# ibmpc.net
KiCad netlist of a schematic drawn in EAGLE
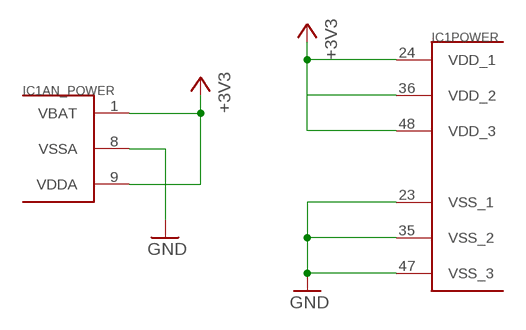
[diagram p0: schematic, sheet 1, part 1 of 2]
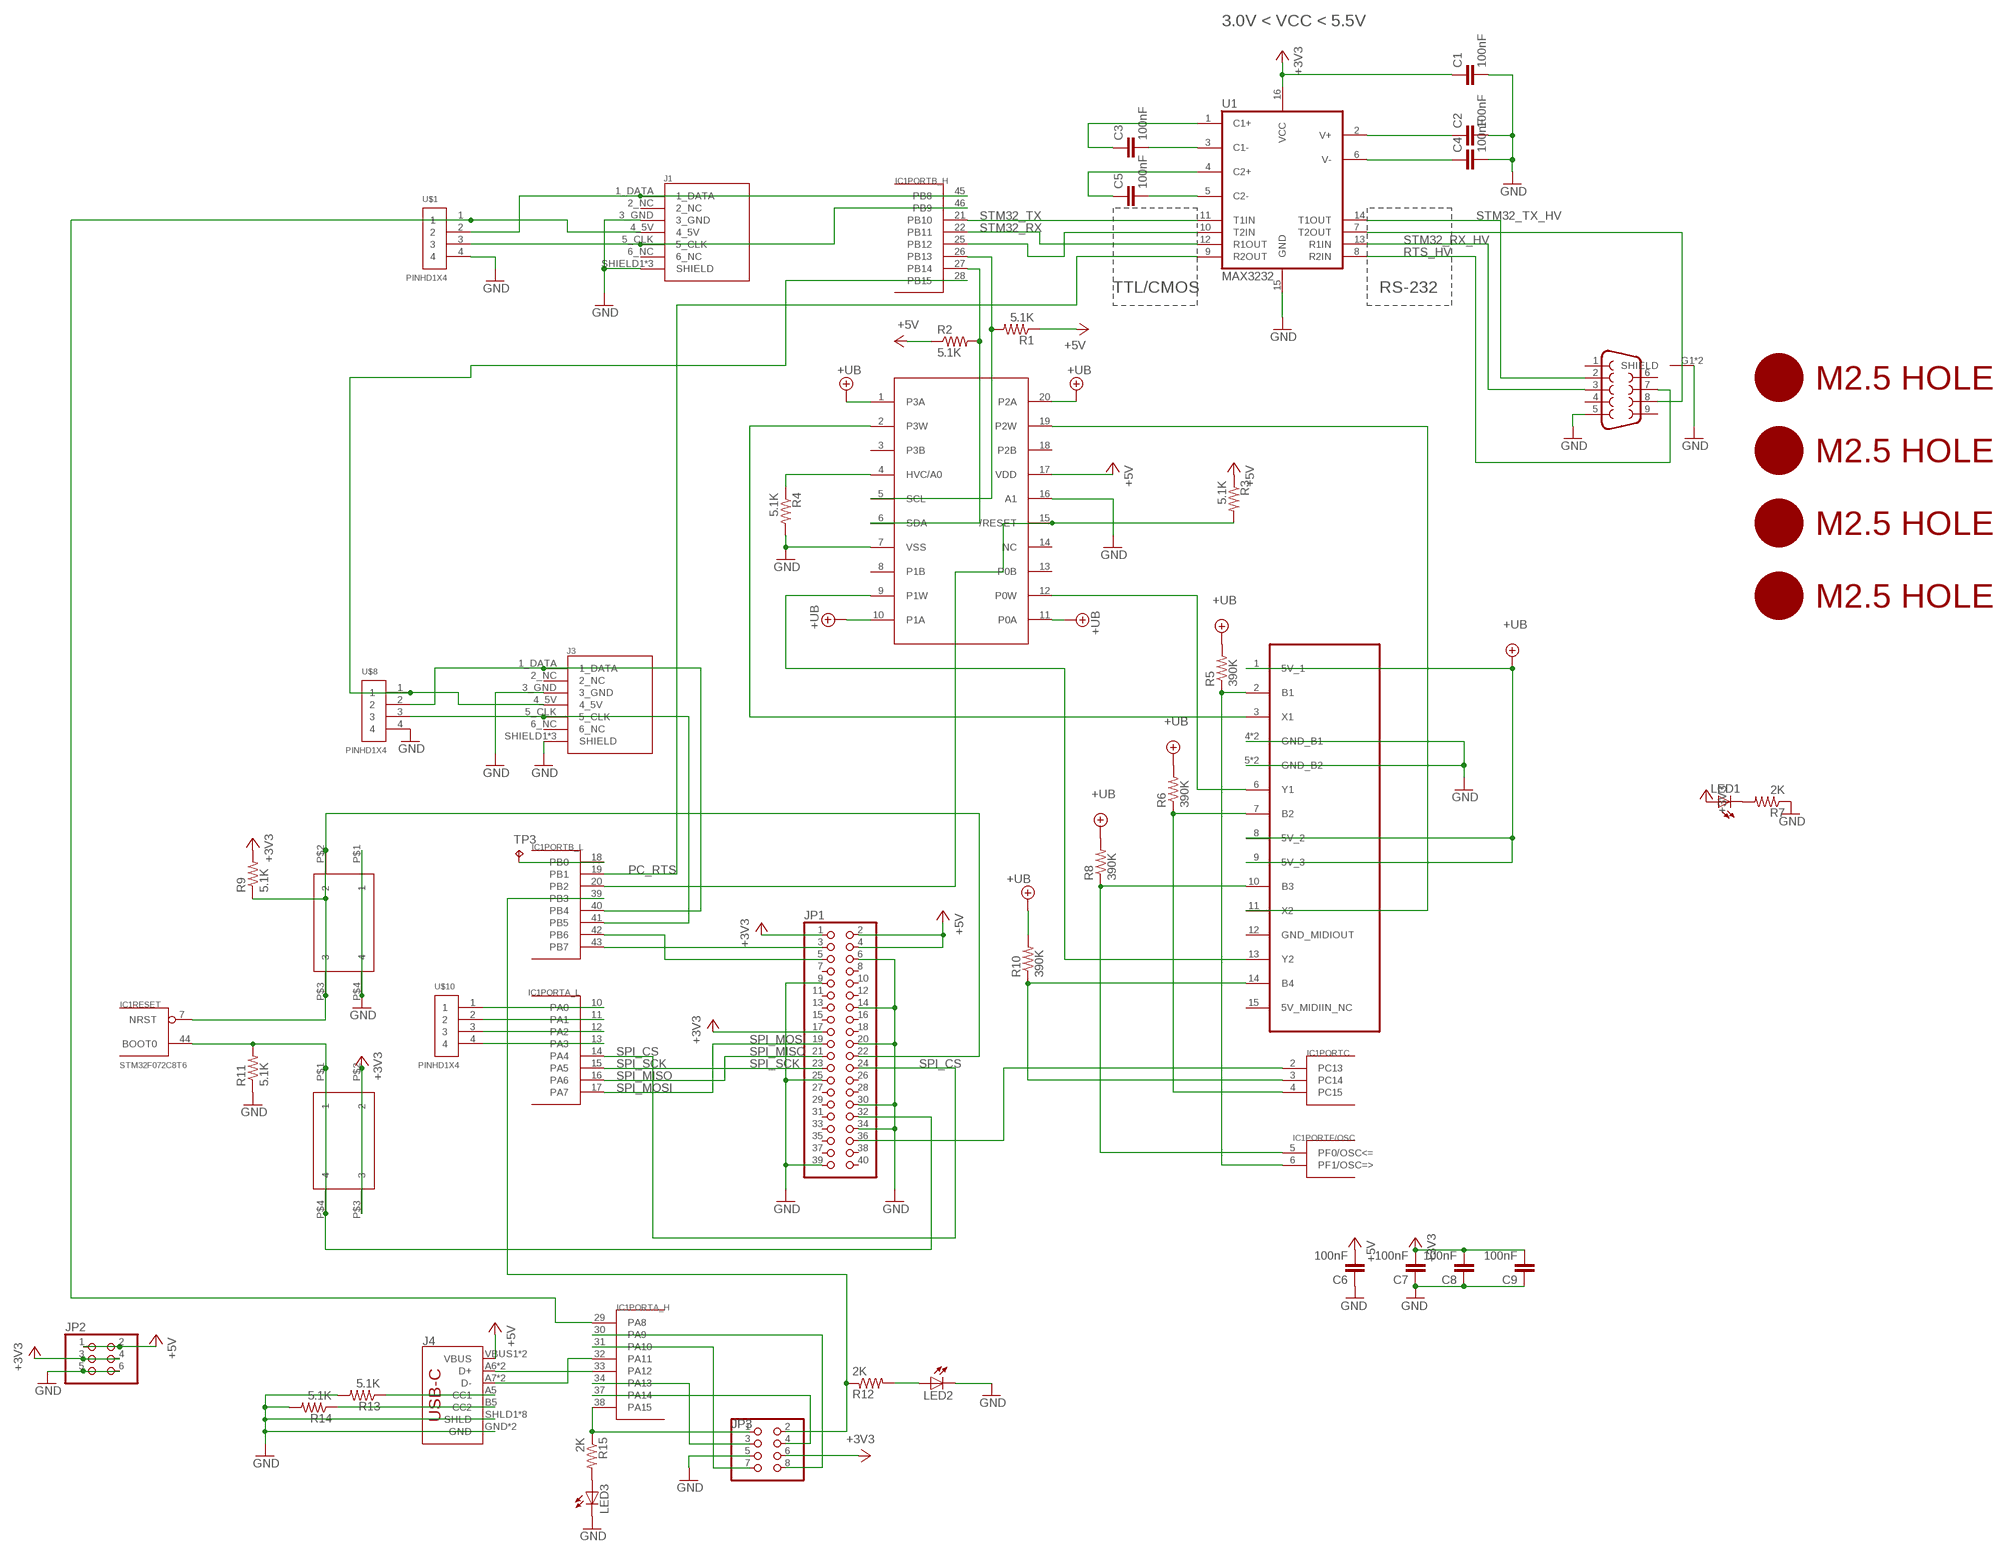
[diagram p1: schematic, sheet 1, part 2 of 2]

(export (version "E")
  (design (tool "Eeschema 10.0.6"))
  (components
    (comp (ref "C1")
      (value "100nF")
      (footprint "eagle-import:0805@1")
      (libsource (lib "eagle-import") (part "CAP0805"))
    )
    (comp (ref "C2")
      (value "100nF")
      (footprint "eagle-import:0805@1")
      (libsource (lib "eagle-import") (part "CAP0805"))
    )
    (comp (ref "C3")
      (value "100nF")
      (footprint "eagle-import:0805@1")
      (libsource (lib "eagle-import") (part "CAP0805"))
    )
    (comp (ref "C4")
      (value "100nF")
      (footprint "eagle-import:0805@1")
      (libsource (lib "eagle-import") (part "CAP0805"))
    )
    (comp (ref "C5")
      (value "100nF")
      (footprint "eagle-import:0805@1")
      (libsource (lib "eagle-import") (part "CAP0805"))
    )
    (comp (ref "C6")
      (value "100nF")
      (footprint "eagle-import:0805@1")
      (libsource (lib "eagle-import") (part "CAP0805"))
    )
    (comp (ref "C7")
      (value "100nF")
      (footprint "eagle-import:0805@1")
      (libsource (lib "eagle-import") (part "CAP0805"))
    )
    (comp (ref "C8")
      (value "100nF")
      (footprint "eagle-import:0805@1")
      (libsource (lib "eagle-import") (part "CAP0805"))
    )
    (comp (ref "C9")
      (value "100nF")
      (footprint "eagle-import:0805@1")
      (libsource (lib "eagle-import") (part "CAP0805"))
    )
    (comp (ref "IC1")
      (value "STM32F072C8T6")
      (footprint "eagle-import:TQFP48")
      (libsource (lib "eagle-import") (part "STM32F072C8T6"))
    )
    (comp (ref "J1")
      (value "DIN7")
      (footprint "eagle-import:DIN7")
      (libsource (lib "eagle-import") (part "DIN7"))
    )
    (comp (ref "J2")
      (value "DB9MALE")
      (footprint "eagle-import:DB9_MALE")
      (libsource (lib "eagle-import") (part "DB9MALE"))
    )
    (comp (ref "J3")
      (value "DIN7")
      (footprint "eagle-import:DIN7")
      (libsource (lib "eagle-import") (part "DIN7"))
    )
    (comp (ref "J4")
      (value "USB_C16PIN")
      (footprint "eagle-import:USB-C-16P")
      (libsource (lib "eagle-import") (part "USB_C16PIN"))
    )
    (comp (ref "JP1")
      (value "PINHD-2X20-BIG")
      (footprint "eagle-import:2X20-BIG")
      (libsource (lib "eagle-import") (part "PINHD-2X20-BIG"))
    )
    (comp (ref "JP2")
      (value "PINHD-2X3")
      (footprint "eagle-import:2X03")
      (libsource (lib "eagle-import") (part "PINHD-2X3"))
    )
    (comp (ref "JP3")
      (value "PINHD-2X4")
      (footprint "eagle-import:2X04")
      (libsource (lib "eagle-import") (part "PINHD-2X4"))
    )
    (comp (ref "LED1")
      (value "LEDCHIP-LED0805")
      (footprint "eagle-import:CHIP-LED0805")
      (libsource (lib "eagle-import") (part "LEDCHIP-LED0805"))
    )
    (comp (ref "LED2")
      (value "LEDCHIP-LED0805")
      (footprint "eagle-import:CHIP-LED0805")
      (libsource (lib "eagle-import") (part "LEDCHIP-LED0805"))
    )
    (comp (ref "LED3")
      (value "LEDCHIP-LED0805")
      (footprint "eagle-import:CHIP-LED0805")
      (libsource (lib "eagle-import") (part "LEDCHIP-LED0805"))
    )
    (comp (ref "R1")
      (value "5.1K")
      (footprint "eagle-import:0805")
      (libsource (lib "eagle-import") (part "RESISTOR0805-RES"))
    )
    (comp (ref "R2")
      (value "5.1K")
      (footprint "eagle-import:0805")
      (libsource (lib "eagle-import") (part "RESISTOR0805-RES"))
    )
    (comp (ref "R3")
      (value "5.1K")
      (footprint "eagle-import:0805")
      (libsource (lib "eagle-import") (part "RESISTOR0805-RES"))
    )
    (comp (ref "R4")
      (value "5.1K")
      (footprint "eagle-import:0805")
      (libsource (lib "eagle-import") (part "RESISTOR0805-RES"))
    )
    (comp (ref "R5")
      (value "390K")
      (footprint "eagle-import:0805")
      (libsource (lib "eagle-import") (part "RESISTOR0805-RES"))
    )
    (comp (ref "R6")
      (value "390K")
      (footprint "eagle-import:0805")
      (libsource (lib "eagle-import") (part "RESISTOR0805-RES"))
    )
    (comp (ref "R7")
      (value "2K")
      (footprint "eagle-import:0805")
      (libsource (lib "eagle-import") (part "RESISTOR0805-RES"))
    )
    (comp (ref "R8")
      (value "390K")
      (footprint "eagle-import:0805")
      (libsource (lib "eagle-import") (part "RESISTOR0805-RES"))
    )
    (comp (ref "R9")
      (value "5.1K")
      (footprint "eagle-import:0805")
      (libsource (lib "eagle-import") (part "RESISTOR0805-RES"))
    )
    (comp (ref "R10")
      (value "390K")
      (footprint "eagle-import:0805")
      (libsource (lib "eagle-import") (part "RESISTOR0805-RES"))
    )
    (comp (ref "R11")
      (value "5.1K")
      (footprint "eagle-import:0805")
      (libsource (lib "eagle-import") (part "RESISTOR0805-RES"))
    )
    (comp (ref "R12")
      (value "2K")
      (footprint "eagle-import:0805")
      (libsource (lib "eagle-import") (part "RESISTOR0805-RES"))
    )
    (comp (ref "R13")
      (value "5.1K")
      (footprint "eagle-import:0805")
      (libsource (lib "eagle-import") (part "RESISTOR0805-RES"))
    )
    (comp (ref "R14")
      (value "5.1K")
      (footprint "eagle-import:0805")
      (libsource (lib "eagle-import") (part "RESISTOR0805-RES"))
    )
    (comp (ref "R15")
      (value "2K")
      (footprint "eagle-import:0805")
      (libsource (lib "eagle-import") (part "RESISTOR0805-RES"))
    )
    (comp (ref "SW1")
      (value "324_SW")
      (footprint "eagle-import:342_SWICH_FOOT")
      (libsource (lib "eagle-import") (part "324_SW"))
    )
    (comp (ref "SW2")
      (value "324_SW")
      (footprint "eagle-import:342_SWICH_FOOT")
      (libsource (lib "eagle-import") (part "324_SW"))
    )
    (comp (ref "TP3")
      (value "TPTP12R")
      (footprint "eagle-import:TP12R")
      (libsource (lib "eagle-import") (part "TPTP12R"))
    )
    (comp (ref "U$1")
      (value "PINHD1X4")
      (footprint "eagle-import:1X04-CLEANBIG")
      (libsource (lib "eagle-import") (part "PINHD1X4"))
    )
    (comp (ref "U$2")
      (value "M2.5HOLE")
      (footprint "eagle-import:M2.5HOLE")
      (libsource (lib "eagle-import") (part "M2.5HOLE"))
    )
    (comp (ref "U$3")
      (value "M2.5HOLE")
      (footprint "eagle-import:M2.5HOLE")
      (libsource (lib "eagle-import") (part "M2.5HOLE"))
    )
    (comp (ref "U$5")
      (value "MCP4451")
      (footprint "eagle-import:TSSOP20")
      (libsource (lib "eagle-import") (part "MCP4451"))
    )
    (comp (ref "U$6")
      (value "M2.5HOLE")
      (footprint "eagle-import:M2.5HOLE")
      (libsource (lib "eagle-import") (part "M2.5HOLE"))
    )
    (comp (ref "U$7")
      (value "M2.5HOLE")
      (footprint "eagle-import:M2.5HOLE")
      (libsource (lib "eagle-import") (part "M2.5HOLE"))
    )
    (comp (ref "U$8")
      (value "PINHD1X4")
      (footprint "eagle-import:1X04-CLEANBIG")
      (libsource (lib "eagle-import") (part "PINHD1X4"))
    )
    (comp (ref "U$9")
      (value "GAMEPORT_15P")
      (footprint "eagle-import:DA15")
      (libsource (lib "eagle-import") (part "GAMEPORT_15P"))
    )
    (comp (ref "U$10")
      (value "PINHD1X4")
      (footprint "eagle-import:1X04-CLEANBIG")
      (libsource (lib "eagle-import") (part "PINHD1X4"))
    )
    (comp (ref "U1")
      (value "MAX3232")
      (footprint "eagle-import:SO016")
      (libsource (lib "eagle-import") (part "MAX232SOIC16"))
    )
  )
  (nets
    (net (code "1") (name "+3V3") (class "Default")
      (node (ref "C1") (pin "1") (pinfunction "1_1") (pintype "passive"))
      (node (ref "C7") (pin "2") (pinfunction "2_2") (pintype "passive"))
      (node (ref "C8") (pin "2") (pinfunction "2_2") (pintype "passive"))
      (node (ref "C9") (pin "2") (pinfunction "2_2") (pintype "passive"))
      (node (ref "IC1") (pin "1") (pinfunction "VBAT_1") (pintype "power_in"))
      (node (ref "IC1") (pin "24") (pinfunction "VDD_1_24") (pintype "power_in"))
      (node (ref "IC1") (pin "36") (pinfunction "VDD_2_36") (pintype "power_in"))
      (node (ref "IC1") (pin "48") (pinfunction "VDD_3_48") (pintype "power_in"))
      (node (ref "IC1") (pin "9") (pinfunction "VDDA_9") (pintype "power_in"))
      (node (ref "JP1") (pin "1") (pinfunction "1_1") (pintype "passive"))
      (node (ref "JP1") (pin "17") (pinfunction "17_17") (pintype "passive"))
      (node (ref "JP2") (pin "3") (pinfunction "3_3") (pintype "passive"))
      (node (ref "JP2") (pin "4") (pinfunction "4_4") (pintype "passive"))
      (node (ref "JP3") (pin "6") (pinfunction "6_6") (pintype "passive"))
      (node (ref "LED1") (pin "A") (pinfunction "A_A") (pintype "passive"))
      (node (ref "R9") (pin "2") (pinfunction "2_2") (pintype "passive"))
      (node (ref "SW2") (pin "P$2") (pinfunction "2_P$2") (pintype "bidirectional"))
      (node (ref "SW2") (pin "P$3") (pinfunction "3_P$3") (pintype "bidirectional"))
      (node (ref "U1") (pin "16") (pinfunction "VCC_16") (pintype "bidirectional"))
    )
    (net (code "2") (name "+5V") (class "Default")
      (node (ref "C6") (pin "2") (pinfunction "2_2") (pintype "passive"))
      (node (ref "J4") (pin "VBUS1") (pinfunction "VBUS_VBUS1") (pintype "bidirectional"))
      (node (ref "J4") (pin "VBUS2") (pinfunction "VBUS_VBUS2") (pintype "bidirectional"))
      (node (ref "JP1") (pin "2") (pinfunction "2_2") (pintype "passive"))
      (node (ref "JP1") (pin "4") (pinfunction "4_4") (pintype "passive"))
      (node (ref "JP2") (pin "1") (pinfunction "1_1") (pintype "passive"))
      (node (ref "JP2") (pin "2") (pinfunction "2_2") (pintype "passive"))
      (node (ref "R1") (pin "1") (pinfunction "1_1") (pintype "passive"))
      (node (ref "R2") (pin "1") (pinfunction "1_1") (pintype "passive"))
      (node (ref "R3") (pin "1") (pinfunction "1_1") (pintype "passive"))
      (node (ref "U$5") (pin "17") (pinfunction "VDD_17") (pintype "bidirectional"))
    )
    (net (code "3") (name "+UB") (class "Default")
      (node (ref "R10") (pin "2") (pinfunction "2_2") (pintype "passive"))
      (node (ref "R5") (pin "2") (pinfunction "2_2") (pintype "passive"))
      (node (ref "R6") (pin "2") (pinfunction "2_2") (pintype "passive"))
      (node (ref "R8") (pin "2") (pinfunction "2_2") (pintype "passive"))
      (node (ref "U$5") (pin "1") (pinfunction "P3A_1") (pintype "bidirectional"))
      (node (ref "U$5") (pin "10") (pinfunction "P1A_10") (pintype "bidirectional"))
      (node (ref "U$5") (pin "11") (pinfunction "P0A_11") (pintype "bidirectional"))
      (node (ref "U$5") (pin "20") (pinfunction "P2A_20") (pintype "bidirectional"))
      (node (ref "U$9") (pin "1") (pinfunction "5V_1_1") (pintype "bidirectional"))
      (node (ref "U$9") (pin "8") (pinfunction "5V_2_8") (pintype "bidirectional"))
      (node (ref "U$9") (pin "9") (pinfunction "5V_3_9") (pintype "bidirectional"))
    )
    (net (code "4") (name "/PC_RTS") (class "Default")
      (node (ref "IC1") (pin "19") (pinfunction "PB1_19") (pintype "bidirectional"))
      (node (ref "U1") (pin "9") (pinfunction "R2OUT_9") (pintype "output"))
    )
    (net (code "5") (name "/RTS_HV") (class "Default")
      (node (ref "J2") (pin "7") (pinfunction "7_7") (pintype "passive"))
      (node (ref "U1") (pin "8") (pinfunction "R2IN_8") (pintype "input"))
    )
    (net (code "6") (name "/SPI_CS") (class "Default")
      (node (ref "IC1") (pin "14") (pinfunction "PA4_14") (pintype "bidirectional"))
      (node (ref "JP1") (pin "24") (pinfunction "24_24") (pintype "passive"))
    )
    (net (code "7") (name "/SPI_MISO") (class "Default")
      (node (ref "IC1") (pin "16") (pinfunction "PA6_16") (pintype "bidirectional"))
      (node (ref "JP1") (pin "21") (pinfunction "21_21") (pintype "passive"))
    )
    (net (code "8") (name "/SPI_MOSI") (class "Default")
      (node (ref "IC1") (pin "17") (pinfunction "PA7_17") (pintype "bidirectional"))
      (node (ref "JP1") (pin "19") (pinfunction "19_19") (pintype "passive"))
    )
    (net (code "9") (name "/SPI_SCK") (class "Default")
      (node (ref "IC1") (pin "15") (pinfunction "PA5_15") (pintype "bidirectional"))
      (node (ref "JP1") (pin "23") (pinfunction "23_23") (pintype "passive"))
    )
    (net (code "10") (name "/STM32_RX") (class "Default")
      (node (ref "IC1") (pin "22") (pinfunction "PB11_22") (pintype "bidirectional"))
      (node (ref "U1") (pin "12") (pinfunction "R1OUT_12") (pintype "output"))
    )
    (net (code "11") (name "/STM32_RX_HV") (class "Default")
      (node (ref "J2") (pin "3") (pinfunction "3_3") (pintype "passive"))
      (node (ref "U1") (pin "13") (pinfunction "R1IN_13") (pintype "input"))
    )
    (net (code "12") (name "/STM32_TX") (class "Default")
      (node (ref "IC1") (pin "21") (pinfunction "PB10_21") (pintype "bidirectional"))
      (node (ref "U1") (pin "11") (pinfunction "T1IN_11") (pintype "input"))
    )
    (net (code "13") (name "/STM32_TX_HV") (class "Default")
      (node (ref "J2") (pin "2") (pinfunction "2_2") (pintype "passive"))
      (node (ref "U1") (pin "14") (pinfunction "T1OUT_14") (pintype "output"))
    )
    (net (code "14") (name "GND") (class "Default")
      (node (ref "C1") (pin "2") (pinfunction "2_2") (pintype "passive"))
      (node (ref "C2") (pin "2") (pinfunction "2_2") (pintype "passive"))
      (node (ref "C4") (pin "2") (pinfunction "2_2") (pintype "passive"))
      (node (ref "C6") (pin "1") (pinfunction "1_1") (pintype "passive"))
      (node (ref "C7") (pin "1") (pinfunction "1_1") (pintype "passive"))
      (node (ref "C8") (pin "1") (pinfunction "1_1") (pintype "passive"))
      (node (ref "C9") (pin "1") (pinfunction "1_1") (pintype "passive"))
      (node (ref "IC1") (pin "23") (pinfunction "VSS_1_23") (pintype "power_in"))
      (node (ref "IC1") (pin "35") (pinfunction "VSS_2_35") (pintype "power_in"))
      (node (ref "IC1") (pin "47") (pinfunction "VSS_3_47") (pintype "power_in"))
      (node (ref "IC1") (pin "8") (pinfunction "VSSA_8") (pintype "power_in"))
      (node (ref "J1") (pin "3_GND") (pinfunction "3_GND_3_GND") (pintype "bidirectional"))
      (node (ref "J1") (pin "SHIELD1") (pinfunction "SHIELD_SHIELD1") (pintype "bidirectional"))
      (node (ref "J1") (pin "SHIELD2") (pinfunction "SHIELD_SHIELD2") (pintype "bidirectional"))
      (node (ref "J1") (pin "SHIELD3") (pinfunction "SHIELD_SHIELD3") (pintype "bidirectional"))
      (node (ref "J2") (pin "5") (pinfunction "5_5") (pintype "passive"))
      (node (ref "J2") (pin "G1") (pinfunction "SHIELD_G1") (pintype "bidirectional"))
      (node (ref "J2") (pin "G2") (pinfunction "SHIELD_G2") (pintype "bidirectional"))
      (node (ref "J3") (pin "3_GND") (pinfunction "3_GND_3_GND") (pintype "bidirectional"))
      (node (ref "J3") (pin "SHIELD1") (pinfunction "SHIELD_SHIELD1") (pintype "bidirectional"))
      (node (ref "J3") (pin "SHIELD2") (pinfunction "SHIELD_SHIELD2") (pintype "bidirectional"))
      (node (ref "J3") (pin "SHIELD3") (pinfunction "SHIELD_SHIELD3") (pintype "bidirectional"))
      (node (ref "J4") (pin "GND") (pinfunction "GND_GND") (pintype "bidirectional"))
      (node (ref "J4") (pin "GND2") (pinfunction "GND_GND2") (pintype "bidirectional"))
      (node (ref "J4") (pin "SHLD1") (pinfunction "SHLD_SHLD1") (pintype "bidirectional"))
      (node (ref "J4") (pin "SHLD2") (pinfunction "SHLD_SHLD2") (pintype "bidirectional"))
      (node (ref "J4") (pin "SHLD3") (pinfunction "SHLD_SHLD3") (pintype "bidirectional"))
      (node (ref "J4") (pin "SHLD4") (pinfunction "SHLD_SHLD4") (pintype "bidirectional"))
      (node (ref "J4") (pin "SHLD5") (pinfunction "SHLD_SHLD5") (pintype "bidirectional"))
      (node (ref "J4") (pin "SHLD6") (pinfunction "SHLD_SHLD6") (pintype "bidirectional"))
      (node (ref "J4") (pin "SHLD7") (pinfunction "SHLD_SHLD7") (pintype "bidirectional"))
      (node (ref "J4") (pin "SHLD8") (pinfunction "SHLD_SHLD8") (pintype "bidirectional"))
      (node (ref "JP1") (pin "14") (pinfunction "14_14") (pintype "passive"))
      (node (ref "JP1") (pin "20") (pinfunction "20_20") (pintype "passive"))
      (node (ref "JP1") (pin "25") (pinfunction "25_25") (pintype "passive"))
      (node (ref "JP1") (pin "30") (pinfunction "30_30") (pintype "passive"))
      (node (ref "JP1") (pin "34") (pinfunction "34_34") (pintype "passive"))
      (node (ref "JP1") (pin "39") (pinfunction "39_39") (pintype "passive"))
      (node (ref "JP1") (pin "6") (pinfunction "6_6") (pintype "passive"))
      (node (ref "JP1") (pin "9") (pinfunction "9_9") (pintype "passive"))
      (node (ref "JP2") (pin "5") (pinfunction "5_5") (pintype "passive"))
      (node (ref "JP2") (pin "6") (pinfunction "6_6") (pintype "passive"))
      (node (ref "JP3") (pin "5") (pinfunction "5_5") (pintype "passive"))
      (node (ref "LED2") (pin "C") (pinfunction "C_C") (pintype "passive"))
      (node (ref "LED3") (pin "C") (pinfunction "C_C") (pintype "passive"))
      (node (ref "R11") (pin "1") (pinfunction "1_1") (pintype "passive"))
      (node (ref "R13") (pin "2") (pinfunction "2_2") (pintype "passive"))
      (node (ref "R14") (pin "2") (pinfunction "2_2") (pintype "passive"))
      (node (ref "R4") (pin "2") (pinfunction "2_2") (pintype "passive"))
      (node (ref "R7") (pin "1") (pinfunction "1_1") (pintype "passive"))
      (node (ref "SW1") (pin "P$1") (pinfunction "1_P$1") (pintype "bidirectional"))
      (node (ref "SW1") (pin "P$4") (pinfunction "4_P$4") (pintype "bidirectional"))
      (node (ref "U$1") (pin "4") (pinfunction "4_4") (pintype "bidirectional"))
      (node (ref "U$5") (pin "16") (pinfunction "A1_16") (pintype "bidirectional"))
      (node (ref "U$5") (pin "7") (pinfunction "VSS_7") (pintype "bidirectional"))
      (node (ref "U$8") (pin "4") (pinfunction "4_4") (pintype "bidirectional"))
      (node (ref "U$9") (pin "4") (pinfunction "GND_B1_4") (pintype "bidirectional"))
      (node (ref "U$9") (pin "5") (pinfunction "GND_B2_5") (pintype "bidirectional"))
      (node (ref "U$9") (pin "G1") (pinfunction "GND_B1_G1") (pintype "bidirectional"))
      (node (ref "U$9") (pin "G2") (pinfunction "GND_B2_G2") (pintype "bidirectional"))
      (node (ref "U1") (pin "15") (pinfunction "GND_15") (pintype "bidirectional"))
    )
    (net (code "15") (name "Net-(IC1B-PA8)") (class "Default")
      (node (ref "IC1") (pin "29") (pinfunction "PA8_29") (pintype "bidirectional"))
      (node (ref "J1") (pin "4_5V") (pinfunction "4_5V_4_5V") (pintype "bidirectional"))
      (node (ref "U$1") (pin "1") (pinfunction "1_1") (pintype "bidirectional"))
    )
    (net (code "16") (name "Net-(IC1B-PA9)") (class "Default")
      (node (ref "IC1") (pin "30") (pinfunction "PA9_30") (pintype "bidirectional"))
      (node (ref "JP3") (pin "8") (pinfunction "8_8") (pintype "passive"))
    )
    (net (code "17") (name "Net-(IC1B-PA10)") (class "Default")
      (node (ref "IC1") (pin "31") (pinfunction "PA10_31") (pintype "bidirectional"))
      (node (ref "JP3") (pin "7") (pinfunction "7_7") (pintype "passive"))
    )
    (net (code "18") (name "Net-(IC1B-PA11)") (class "Default")
      (node (ref "IC1") (pin "32") (pinfunction "PA11_32") (pintype "bidirectional"))
      (node (ref "J4") (pin "A7") (pinfunction "D-_A7") (pintype "bidirectional"))
      (node (ref "J4") (pin "B7") (pinfunction "D-_B7") (pintype "bidirectional"))
    )
    (net (code "19") (name "Net-(IC1B-PA12)") (class "Default")
      (node (ref "IC1") (pin "33") (pinfunction "PA12_33") (pintype "bidirectional"))
      (node (ref "J4") (pin "A6") (pinfunction "D+_A6") (pintype "bidirectional"))
      (node (ref "J4") (pin "B6") (pinfunction "D+_B6") (pintype "bidirectional"))
    )
    (net (code "20") (name "Net-(IC1B-PA13)") (class "Default")
      (node (ref "IC1") (pin "34") (pinfunction "PA13_34") (pintype "bidirectional"))
      (node (ref "JP3") (pin "3") (pinfunction "3_3") (pintype "passive"))
    )
    (net (code "21") (name "Net-(IC1B-PA14)") (class "Default")
      (node (ref "IC1") (pin "37") (pinfunction "PA14_37") (pintype "bidirectional"))
      (node (ref "JP3") (pin "4") (pinfunction "4_4") (pintype "passive"))
    )
    (net (code "22") (name "Net-(IC1B-PA15)") (class "Default")
      (node (ref "IC1") (pin "38") (pinfunction "PA15_38") (pintype "bidirectional"))
      (node (ref "JP3") (pin "1") (pinfunction "1_1") (pintype "passive"))
      (node (ref "R15") (pin "1") (pinfunction "1_1") (pintype "passive"))
    )
    (net (code "23") (name "Net-(IC1C-PA0)") (class "Default")
      (node (ref "IC1") (pin "10") (pinfunction "PA0_10") (pintype "bidirectional"))
      (node (ref "U$10") (pin "1") (pinfunction "1_1") (pintype "bidirectional"))
    )
    (net (code "24") (name "Net-(IC1C-PA1)") (class "Default")
      (node (ref "IC1") (pin "11") (pinfunction "PA1_11") (pintype "bidirectional"))
      (node (ref "U$10") (pin "2") (pinfunction "2_2") (pintype "bidirectional"))
    )
    (net (code "25") (name "Net-(IC1C-PA2)") (class "Default")
      (node (ref "IC1") (pin "12") (pinfunction "PA2_12") (pintype "bidirectional"))
      (node (ref "U$10") (pin "3") (pinfunction "3_3") (pintype "bidirectional"))
    )
    (net (code "26") (name "Net-(IC1C-PA3)") (class "Default")
      (node (ref "IC1") (pin "13") (pinfunction "PA3_13") (pintype "bidirectional"))
      (node (ref "U$10") (pin "4") (pinfunction "4_4") (pintype "bidirectional"))
    )
    (net (code "27") (name "Net-(IC1D-PB8)") (class "Default")
      (node (ref "IC1") (pin "45") (pinfunction "PB8_45") (pintype "bidirectional"))
      (node (ref "J1") (pin "1_DATA") (pinfunction "1_DATA_1_DATA") (pintype "bidirectional"))
      (node (ref "U$1") (pin "2") (pinfunction "2_2") (pintype "bidirectional"))
    )
    (net (code "28") (name "Net-(IC1D-PB9)") (class "Default")
      (node (ref "IC1") (pin "46") (pinfunction "PB9_46") (pintype "bidirectional"))
      (node (ref "J1") (pin "5_CLK") (pinfunction "5_CLK_5_CLK") (pintype "bidirectional"))
      (node (ref "U$1") (pin "3") (pinfunction "3_3") (pintype "bidirectional"))
    )
    (net (code "29") (name "Net-(IC1D-PB12)") (class "Default")
      (node (ref "IC1") (pin "25") (pinfunction "PB12_25") (pintype "bidirectional"))
      (node (ref "U1") (pin "10") (pinfunction "T2IN_10") (pintype "input"))
    )
    (net (code "30") (name "Net-(IC1D-PB13)") (class "Default")
      (node (ref "IC1") (pin "26") (pinfunction "PB13_26") (pintype "bidirectional"))
      (node (ref "R1") (pin "2") (pinfunction "2_2") (pintype "passive"))
      (node (ref "U$5") (pin "5") (pinfunction "SCL_5") (pintype "bidirectional"))
    )
    (net (code "31") (name "Net-(IC1D-PB14)") (class "Default")
      (node (ref "IC1") (pin "27") (pinfunction "PB14_27") (pintype "bidirectional"))
      (node (ref "R2") (pin "2") (pinfunction "2_2") (pintype "passive"))
      (node (ref "U$5") (pin "6") (pinfunction "SDA_6") (pintype "bidirectional"))
    )
    (net (code "32") (name "Net-(IC1D-PB15)") (class "Default")
      (node (ref "IC1") (pin "28") (pinfunction "PB15_28") (pintype "bidirectional"))
      (node (ref "J3") (pin "4_5V") (pinfunction "4_5V_4_5V") (pintype "bidirectional"))
      (node (ref "U$8") (pin "1") (pinfunction "1_1") (pintype "bidirectional"))
    )
    (net (code "33") (name "Net-(IC1E-PB0)") (class "Default")
      (node (ref "IC1") (pin "18") (pinfunction "PB0_18") (pintype "bidirectional"))
      (node (ref "TP3") (pin "TP") (pinfunction "TP_TP") (pintype "input"))
    )
    (net (code "34") (name "Net-(IC1E-PB2)") (class "Default")
      (node (ref "IC1") (pin "20") (pinfunction "PB2_20") (pintype "bidirectional"))
      (node (ref "R3") (pin "2") (pinfunction "2_2") (pintype "passive"))
      (node (ref "U$5") (pin "15") (pinfunction "/RESET_15") (pintype "bidirectional"))
    )
    (net (code "35") (name "Net-(IC1E-PB3)") (class "Default")
      (node (ref "IC1") (pin "39") (pinfunction "PB3_39") (pintype "bidirectional"))
      (node (ref "JP3") (pin "2") (pinfunction "2_2") (pintype "passive"))
      (node (ref "R12") (pin "1") (pinfunction "1_1") (pintype "passive"))
    )
    (net (code "36") (name "Net-(IC1E-PB4)") (class "Default")
      (node (ref "IC1") (pin "40") (pinfunction "PB4_40") (pintype "bidirectional"))
      (node (ref "J3") (pin "1_DATA") (pinfunction "1_DATA_1_DATA") (pintype "bidirectional"))
      (node (ref "U$8") (pin "2") (pinfunction "2_2") (pintype "bidirectional"))
    )
    (net (code "37") (name "Net-(IC1E-PB5)") (class "Default")
      (node (ref "IC1") (pin "41") (pinfunction "PB5_41") (pintype "bidirectional"))
      (node (ref "J3") (pin "5_CLK") (pinfunction "5_CLK_5_CLK") (pintype "bidirectional"))
      (node (ref "U$8") (pin "3") (pinfunction "3_3") (pintype "bidirectional"))
    )
    (net (code "38") (name "Net-(IC1E-PB6)") (class "Default")
      (node (ref "IC1") (pin "42") (pinfunction "PB6_42") (pintype "bidirectional"))
      (node (ref "JP1") (pin "5") (pinfunction "5_5") (pintype "passive"))
    )
    (net (code "39") (name "Net-(IC1E-PB7)") (class "Default")
      (node (ref "IC1") (pin "43") (pinfunction "PB7_43") (pintype "bidirectional"))
      (node (ref "JP1") (pin "3") (pinfunction "3_3") (pintype "passive"))
    )
    (net (code "40") (name "Net-(IC1F-PC13)") (class "Default")
      (node (ref "IC1") (pin "2") (pinfunction "PC13_2") (pintype "bidirectional"))
      (node (ref "JP1") (pin "36") (pinfunction "36_36") (pintype "passive"))
    )
    (net (code "41") (name "Net-(IC1F-PC14)") (class "Default")
      (node (ref "IC1") (pin "3") (pinfunction "PC14_3") (pintype "bidirectional"))
      (node (ref "R10") (pin "1") (pinfunction "1_1") (pintype "passive"))
      (node (ref "U$9") (pin "14") (pinfunction "B4_14") (pintype "bidirectional"))
    )
    (net (code "42") (name "Net-(IC1F-PC15)") (class "Default")
      (node (ref "IC1") (pin "4") (pinfunction "PC15_4") (pintype "bidirectional"))
      (node (ref "R6") (pin "1") (pinfunction "1_1") (pintype "passive"))
      (node (ref "U$9") (pin "7") (pinfunction "B2_7") (pintype "bidirectional"))
    )
    (net (code "43") (name "Net-(IC1G-PF0{slash}OSC<=)") (class "Default")
      (node (ref "IC1") (pin "5") (pinfunction "PF0/OSC<=_5") (pintype "bidirectional"))
      (node (ref "R8") (pin "1") (pinfunction "1_1") (pintype "passive"))
      (node (ref "U$9") (pin "10") (pinfunction "B3_10") (pintype "bidirectional"))
    )
    (net (code "44") (name "Net-(IC1G-PF1{slash}OSC=>)") (class "Default")
      (node (ref "IC1") (pin "6") (pinfunction "PF1/OSC=>_6") (pintype "bidirectional"))
      (node (ref "R5") (pin "1") (pinfunction "1_1") (pintype "passive"))
      (node (ref "U$9") (pin "2") (pinfunction "B1_2") (pintype "bidirectional"))
    )
    (net (code "45") (name "Net-(IC1I-BOOT0)") (class "Default")
      (node (ref "IC1") (pin "44") (pinfunction "BOOT0_44") (pintype "input"))
      (node (ref "JP1") (pin "32") (pinfunction "32_32") (pintype "passive"))
      (node (ref "R11") (pin "2") (pinfunction "2_2") (pintype "passive"))
      (node (ref "SW2") (pin "P$1") (pinfunction "1_P$1") (pintype "bidirectional"))
      (node (ref "SW2") (pin "P$4") (pinfunction "4_P$4") (pintype "bidirectional"))
    )
    (net (code "46") (name "Net-(IC1I-NRST)") (class "Default")
      (node (ref "IC1") (pin "7") (pinfunction "NRST_7") (pintype "input"))
      (node (ref "JP1") (pin "22") (pinfunction "22_22") (pintype "passive"))
      (node (ref "R9") (pin "1") (pinfunction "1_1") (pintype "passive"))
      (node (ref "SW1") (pin "P$2") (pinfunction "2_P$2") (pintype "bidirectional"))
      (node (ref "SW1") (pin "P$3") (pinfunction "3_P$3") (pintype "bidirectional"))
    )
    (net (code "47") (name "Net-(J4-CC1)") (class "Default")
      (node (ref "J4") (pin "A5") (pinfunction "CC1_A5") (pintype "bidirectional"))
      (node (ref "R13") (pin "1") (pinfunction "1_1") (pintype "passive"))
    )
    (net (code "48") (name "Net-(J4-CC2)") (class "Default")
      (node (ref "J4") (pin "B5") (pinfunction "CC2_B5") (pintype "bidirectional"))
      (node (ref "R14") (pin "1") (pinfunction "1_1") (pintype "passive"))
    )
    (net (code "49") (name "Net-(LED1-PadC)") (class "Default")
      (node (ref "LED1") (pin "C") (pinfunction "C_C") (pintype "passive"))
      (node (ref "R7") (pin "2") (pinfunction "2_2") (pintype "passive"))
    )
    (net (code "50") (name "Net-(LED2-PadA)") (class "Default")
      (node (ref "LED2") (pin "A") (pinfunction "A_A") (pintype "passive"))
      (node (ref "R12") (pin "2") (pinfunction "2_2") (pintype "passive"))
    )
    (net (code "51") (name "Net-(LED3-PadA)") (class "Default")
      (node (ref "LED3") (pin "A") (pinfunction "A_A") (pintype "passive"))
      (node (ref "R15") (pin "2") (pinfunction "2_2") (pintype "passive"))
    )
    (net (code "52") (name "Net-(U$5-HVC{slash}A0)") (class "Default")
      (node (ref "R4") (pin "1") (pinfunction "1_1") (pintype "passive"))
      (node (ref "U$5") (pin "4") (pinfunction "HVC/A0_4") (pintype "bidirectional"))
    )
    (net (code "53") (name "Net-(U$5-P0W)") (class "Default")
      (node (ref "U$5") (pin "12") (pinfunction "P0W_12") (pintype "bidirectional"))
      (node (ref "U$9") (pin "6") (pinfunction "Y1_6") (pintype "bidirectional"))
    )
    (net (code "54") (name "Net-(U$5-P1W)") (class "Default")
      (node (ref "U$5") (pin "9") (pinfunction "P1W_9") (pintype "bidirectional"))
      (node (ref "U$9") (pin "13") (pinfunction "Y2_13") (pintype "bidirectional"))
    )
    (net (code "55") (name "Net-(U$5-P2W)") (class "Default")
      (node (ref "U$5") (pin "19") (pinfunction "P2W_19") (pintype "bidirectional"))
      (node (ref "U$9") (pin "11") (pinfunction "X2_11") (pintype "bidirectional"))
    )
    (net (code "56") (name "Net-(U$5-P3W)") (class "Default")
      (node (ref "U$5") (pin "2") (pinfunction "P3W_2") (pintype "bidirectional"))
      (node (ref "U$9") (pin "3") (pinfunction "X1_3") (pintype "bidirectional"))
    )
    (net (code "57") (name "Net-(U1-C1+)") (class "Default")
      (node (ref "C3") (pin "1") (pinfunction "1_1") (pintype "passive"))
      (node (ref "U1") (pin "1") (pinfunction "C1+_1") (pintype "bidirectional"))
    )
    (net (code "58") (name "Net-(U1-C1-)") (class "Default")
      (node (ref "C3") (pin "2") (pinfunction "2_2") (pintype "passive"))
      (node (ref "U1") (pin "3") (pinfunction "C1-_3") (pintype "bidirectional"))
    )
    (net (code "59") (name "Net-(U1-C2+)") (class "Default")
      (node (ref "C5") (pin "1") (pinfunction "1_1") (pintype "passive"))
      (node (ref "U1") (pin "4") (pinfunction "C2+_4") (pintype "bidirectional"))
    )
    (net (code "60") (name "Net-(U1-C2-)") (class "Default")
      (node (ref "C5") (pin "2") (pinfunction "2_2") (pintype "passive"))
      (node (ref "U1") (pin "5") (pinfunction "C2-_5") (pintype "bidirectional"))
    )
    (net (code "61") (name "Net-(U1-T2OUT)") (class "Default")
      (node (ref "J2") (pin "8") (pinfunction "8_8") (pintype "passive"))
      (node (ref "U1") (pin "7") (pinfunction "T2OUT_7") (pintype "output"))
    )
    (net (code "62") (name "Net-(U1-V+)") (class "Default")
      (node (ref "C2") (pin "1") (pinfunction "1_1") (pintype "passive"))
      (node (ref "U1") (pin "2") (pinfunction "V+_2") (pintype "bidirectional"))
    )
    (net (code "63") (name "Net-(U1-V-)") (class "Default")
      (node (ref "C4") (pin "1") (pinfunction "1_1") (pintype "passive"))
      (node (ref "U1") (pin "6") (pinfunction "V-_6") (pintype "bidirectional"))
    )
    (net (code "64") (name "unconnected-(J1-Pad2_NC)") (class "Default")
      (node (ref "J1") (pin "2_NC") (pinfunction "2_NC_2_NC") (pintype "bidirectional"))
    )
    (net (code "65") (name "unconnected-(J1-Pad6_NC)") (class "Default")
      (node (ref "J1") (pin "6_NC") (pinfunction "6_NC_6_NC") (pintype "bidirectional"))
    )
    (net (code "66") (name "unconnected-(J2-Pad1)") (class "Default")
      (node (ref "J2") (pin "1") (pinfunction "1_1") (pintype "passive"))
    )
    (net (code "67") (name "unconnected-(J2-Pad4)") (class "Default")
      (node (ref "J2") (pin "4") (pinfunction "4_4") (pintype "passive"))
    )
    (net (code "68") (name "unconnected-(J2-Pad6)") (class "Default")
      (node (ref "J2") (pin "6") (pinfunction "6_6") (pintype "passive"))
    )
    (net (code "69") (name "unconnected-(J2-Pad9)") (class "Default")
      (node (ref "J2") (pin "9") (pinfunction "9_9") (pintype "passive"))
    )
    (net (code "70") (name "unconnected-(J3-Pad2_NC)") (class "Default")
      (node (ref "J3") (pin "2_NC") (pinfunction "2_NC_2_NC") (pintype "bidirectional"))
    )
    (net (code "71") (name "unconnected-(J3-Pad6_NC)") (class "Default")
      (node (ref "J3") (pin "6_NC") (pinfunction "6_NC_6_NC") (pintype "bidirectional"))
    )
    (net (code "72") (name "unconnected-(JP1-Pad7)") (class "Default")
      (node (ref "JP1") (pin "7") (pinfunction "7_7") (pintype "passive"))
    )
    (net (code "73") (name "unconnected-(JP1-Pad8)") (class "Default")
      (node (ref "JP1") (pin "8") (pinfunction "8_8") (pintype "passive"))
    )
    (net (code "74") (name "unconnected-(JP1-Pad10)") (class "Default")
      (node (ref "JP1") (pin "10") (pinfunction "10_10") (pintype "passive"))
    )
    (net (code "75") (name "unconnected-(JP1-Pad11)") (class "Default")
      (node (ref "JP1") (pin "11") (pinfunction "11_11") (pintype "passive"))
    )
    (net (code "76") (name "unconnected-(JP1-Pad12)") (class "Default")
      (node (ref "JP1") (pin "12") (pinfunction "12_12") (pintype "passive"))
    )
    (net (code "77") (name "unconnected-(JP1-Pad13)") (class "Default")
      (node (ref "JP1") (pin "13") (pinfunction "13_13") (pintype "passive"))
    )
    (net (code "78") (name "unconnected-(JP1-Pad15)") (class "Default")
      (node (ref "JP1") (pin "15") (pinfunction "15_15") (pintype "passive"))
    )
    (net (code "79") (name "unconnected-(JP1-Pad16)") (class "Default")
      (node (ref "JP1") (pin "16") (pinfunction "16_16") (pintype "passive"))
    )
    (net (code "80") (name "unconnected-(JP1-Pad18)") (class "Default")
      (node (ref "JP1") (pin "18") (pinfunction "18_18") (pintype "passive"))
    )
    (net (code "81") (name "unconnected-(JP1-Pad26)") (class "Default")
      (node (ref "JP1") (pin "26") (pinfunction "26_26") (pintype "passive"))
    )
    (net (code "82") (name "unconnected-(JP1-Pad27)") (class "Default")
      (node (ref "JP1") (pin "27") (pinfunction "27_27") (pintype "passive"))
    )
    (net (code "83") (name "unconnected-(JP1-Pad28)") (class "Default")
      (node (ref "JP1") (pin "28") (pinfunction "28_28") (pintype "passive"))
    )
    (net (code "84") (name "unconnected-(JP1-Pad29)") (class "Default")
      (node (ref "JP1") (pin "29") (pinfunction "29_29") (pintype "passive"))
    )
    (net (code "85") (name "unconnected-(JP1-Pad31)") (class "Default")
      (node (ref "JP1") (pin "31") (pinfunction "31_31") (pintype "passive"))
    )
    (net (code "86") (name "unconnected-(JP1-Pad33)") (class "Default")
      (node (ref "JP1") (pin "33") (pinfunction "33_33") (pintype "passive"))
    )
    (net (code "87") (name "unconnected-(JP1-Pad35)") (class "Default")
      (node (ref "JP1") (pin "35") (pinfunction "35_35") (pintype "passive"))
    )
    (net (code "88") (name "unconnected-(JP1-Pad37)") (class "Default")
      (node (ref "JP1") (pin "37") (pinfunction "37_37") (pintype "passive"))
    )
    (net (code "89") (name "unconnected-(JP1-Pad38)") (class "Default")
      (node (ref "JP1") (pin "38") (pinfunction "38_38") (pintype "passive"))
    )
    (net (code "90") (name "unconnected-(JP1-Pad40)") (class "Default")
      (node (ref "JP1") (pin "40") (pinfunction "40_40") (pintype "passive"))
    )
    (net (code "91") (name "unconnected-(U$5-NC-Pad14)") (class "Default")
      (node (ref "U$5") (pin "14") (pinfunction "NC_14") (pintype "bidirectional"))
    )
    (net (code "92") (name "unconnected-(U$5-P0B-Pad13)") (class "Default")
      (node (ref "U$5") (pin "13") (pinfunction "P0B_13") (pintype "bidirectional"))
    )
    (net (code "93") (name "unconnected-(U$5-P1B-Pad8)") (class "Default")
      (node (ref "U$5") (pin "8") (pinfunction "P1B_8") (pintype "bidirectional"))
    )
    (net (code "94") (name "unconnected-(U$5-P2B-Pad18)") (class "Default")
      (node (ref "U$5") (pin "18") (pinfunction "P2B_18") (pintype "bidirectional"))
    )
    (net (code "95") (name "unconnected-(U$5-P3B-Pad3)") (class "Default")
      (node (ref "U$5") (pin "3") (pinfunction "P3B_3") (pintype "bidirectional"))
    )
    (net (code "96") (name "unconnected-(U$9-5V_MIDIIN_NC-Pad15)") (class "Default")
      (node (ref "U$9") (pin "15") (pinfunction "5V_MIDIIN_NC_15") (pintype "bidirectional"))
    )
    (net (code "97") (name "unconnected-(U$9-GND_MIDIOUT-Pad12)") (class "Default")
      (node (ref "U$9") (pin "12") (pinfunction "GND_MIDIOUT_12") (pintype "bidirectional"))
    )
  )
)
